# DiffAmp.net
KiCad netlist of a schematic drawn in EAGLE
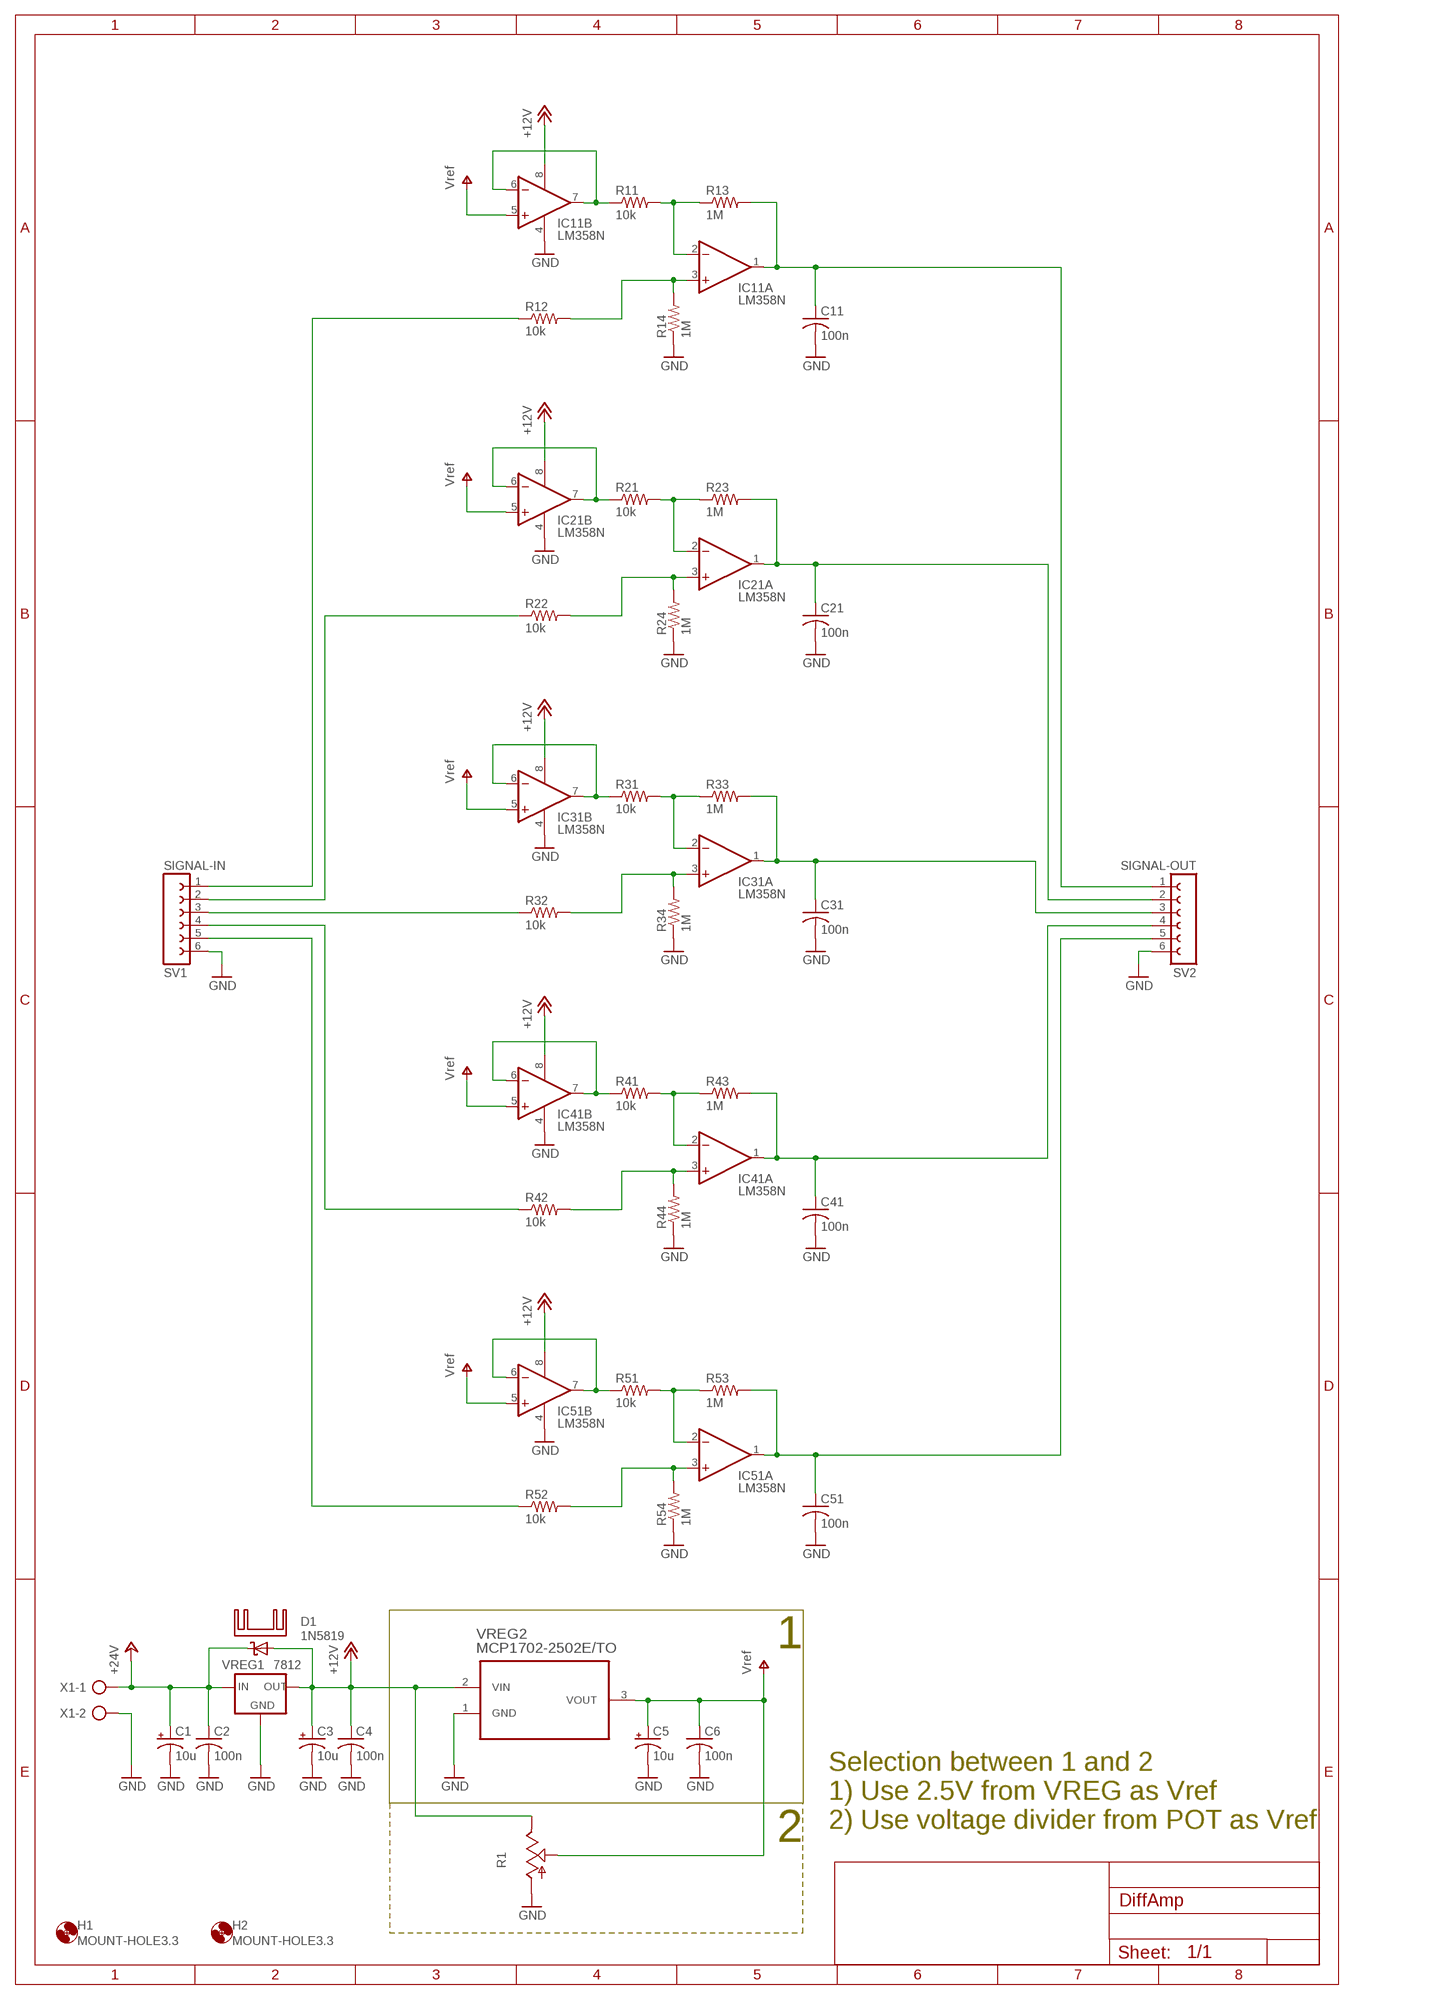
[diagram p0: schematic, sheet 1]

(export (version "E")
  (design (tool "Eeschema 10.0.6"))
  (components
    (comp (ref "C1")
      (value "10u")
      (footprint "eagle-import:E2-5")
      (libsource (lib "eagle-import") (part "CPOL-USE2-5"))
    )
    (comp (ref "C2")
      (value "100n")
      (footprint "eagle-import:C050-025X075")
      (libsource (lib "eagle-import") (part "C-US050-025X075"))
    )
    (comp (ref "C3")
      (value "10u")
      (footprint "eagle-import:E2-5")
      (libsource (lib "eagle-import") (part "CPOL-USE2-5"))
    )
    (comp (ref "C4")
      (value "100n")
      (footprint "eagle-import:C050-025X075")
      (libsource (lib "eagle-import") (part "C-US050-025X075"))
    )
    (comp (ref "C5")
      (value "10u")
      (footprint "eagle-import:E2-5")
      (libsource (lib "eagle-import") (part "CPOL-USE2-5"))
    )
    (comp (ref "C6")
      (value "100n")
      (footprint "eagle-import:C050-025X075")
      (libsource (lib "eagle-import") (part "C-US050-025X075"))
    )
    (comp (ref "C11")
      (value "100n")
      (footprint "eagle-import:C050-025X075")
      (libsource (lib "eagle-import") (part "C-US050-025X075"))
    )
    (comp (ref "C21")
      (value "100n")
      (footprint "eagle-import:C050-025X075")
      (libsource (lib "eagle-import") (part "C-US050-025X075"))
    )
    (comp (ref "C31")
      (value "100n")
      (footprint "eagle-import:C050-025X075")
      (libsource (lib "eagle-import") (part "C-US050-025X075"))
    )
    (comp (ref "C41")
      (value "100n")
      (footprint "eagle-import:C050-025X075")
      (libsource (lib "eagle-import") (part "C-US050-025X075"))
    )
    (comp (ref "C51")
      (value "100n")
      (footprint "eagle-import:C050-025X075")
      (libsource (lib "eagle-import") (part "C-US050-025X075"))
    )
    (comp (ref "D1")
      (value "1N5819")
      (footprint "eagle-import:DO35-7")
      (libsource (lib "eagle-import") (part "SCHOTTKY-DIODEDO35-7"))
    )
    (comp (ref "H1")
      (value "MOUNT-HOLE3.3")
      (footprint "eagle-import:3,3")
      (libsource (lib "eagle-import") (part "MOUNT-HOLE3.3"))
    )
    (comp (ref "H2")
      (value "MOUNT-HOLE3.3")
      (footprint "eagle-import:3,3")
      (libsource (lib "eagle-import") (part "MOUNT-HOLE3.3"))
    )
    (comp (ref "IC11")
      (value "LM358N")
      (footprint "eagle-import:DIL08")
      (libsource (lib "eagle-import") (part "LM358N"))
    )
    (comp (ref "IC21")
      (value "LM358N")
      (footprint "eagle-import:DIL08")
      (libsource (lib "eagle-import") (part "LM358N"))
    )
    (comp (ref "IC31")
      (value "LM358N")
      (footprint "eagle-import:DIL08")
      (libsource (lib "eagle-import") (part "LM358N"))
    )
    (comp (ref "IC41")
      (value "LM358N")
      (footprint "eagle-import:DIL08")
      (libsource (lib "eagle-import") (part "LM358N"))
    )
    (comp (ref "IC51")
      (value "LM358N")
      (footprint "eagle-import:DIL08")
      (libsource (lib "eagle-import") (part "LM358N"))
    )
    (comp (ref "KK1")
      (value "SK95-2M3")
      (footprint "eagle-import:SK95-2M3")
      (libsource (lib "eagle-import") (part "SK95-2M3"))
    )
    (comp (ref "R1")
      (value "TRIM_US-S64W")
      (footprint "eagle-import:S64W")
      (libsource (lib "eagle-import") (part "TRIM_US-S64W"))
    )
    (comp (ref "R11")
      (value "10k")
      (footprint "eagle-import:0207_7")
      (libsource (lib "eagle-import") (part "R-US_0207/7"))
    )
    (comp (ref "R12")
      (value "10k")
      (footprint "eagle-import:0207_7")
      (libsource (lib "eagle-import") (part "R-US_0207/7"))
    )
    (comp (ref "R13")
      (value "1M")
      (footprint "eagle-import:0207_7")
      (libsource (lib "eagle-import") (part "R-US_0207/7"))
    )
    (comp (ref "R14")
      (value "1M")
      (footprint "eagle-import:0207_7")
      (libsource (lib "eagle-import") (part "R-US_0207/7"))
    )
    (comp (ref "R21")
      (value "10k")
      (footprint "eagle-import:0207_7")
      (libsource (lib "eagle-import") (part "R-US_0207/7"))
    )
    (comp (ref "R22")
      (value "10k")
      (footprint "eagle-import:0207_7")
      (libsource (lib "eagle-import") (part "R-US_0207/7"))
    )
    (comp (ref "R23")
      (value "1M")
      (footprint "eagle-import:0207_7")
      (libsource (lib "eagle-import") (part "R-US_0207/7"))
    )
    (comp (ref "R24")
      (value "1M")
      (footprint "eagle-import:0207_7")
      (libsource (lib "eagle-import") (part "R-US_0207/7"))
    )
    (comp (ref "R31")
      (value "10k")
      (footprint "eagle-import:0207_7")
      (libsource (lib "eagle-import") (part "R-US_0207/7"))
    )
    (comp (ref "R32")
      (value "10k")
      (footprint "eagle-import:0207_7")
      (libsource (lib "eagle-import") (part "R-US_0207/7"))
    )
    (comp (ref "R33")
      (value "1M")
      (footprint "eagle-import:0207_7")
      (libsource (lib "eagle-import") (part "R-US_0207/7"))
    )
    (comp (ref "R34")
      (value "1M")
      (footprint "eagle-import:0207_7")
      (libsource (lib "eagle-import") (part "R-US_0207/7"))
    )
    (comp (ref "R41")
      (value "10k")
      (footprint "eagle-import:0207_7")
      (libsource (lib "eagle-import") (part "R-US_0207/7"))
    )
    (comp (ref "R42")
      (value "10k")
      (footprint "eagle-import:0207_7")
      (libsource (lib "eagle-import") (part "R-US_0207/7"))
    )
    (comp (ref "R43")
      (value "1M")
      (footprint "eagle-import:0207_7")
      (libsource (lib "eagle-import") (part "R-US_0207/7"))
    )
    (comp (ref "R44")
      (value "1M")
      (footprint "eagle-import:0207_7")
      (libsource (lib "eagle-import") (part "R-US_0207/7"))
    )
    (comp (ref "R51")
      (value "10k")
      (footprint "eagle-import:0207_7")
      (libsource (lib "eagle-import") (part "R-US_0207/7"))
    )
    (comp (ref "R52")
      (value "10k")
      (footprint "eagle-import:0207_7")
      (libsource (lib "eagle-import") (part "R-US_0207/7"))
    )
    (comp (ref "R53")
      (value "1M")
      (footprint "eagle-import:0207_7")
      (libsource (lib "eagle-import") (part "R-US_0207/7"))
    )
    (comp (ref "R54")
      (value "1M")
      (footprint "eagle-import:0207_7")
      (libsource (lib "eagle-import") (part "R-US_0207/7"))
    )
    (comp (ref "SV1")
      (value "SIGNAL-IN")
      (footprint "eagle-import:FE06")
      (libsource (lib "eagle-import") (part "FE06-1"))
    )
    (comp (ref "SV2")
      (value "SIGNAL-OUT")
      (footprint "eagle-import:FE06")
      (libsource (lib "eagle-import") (part "FE06-1"))
    )
    (comp (ref "VREG1")
      (value "7812")
      (footprint "eagle-import:78XXS")
      (libsource (lib "eagle-import") (part "78XXS"))
    )
    (comp (ref "VREG2")
      (value "MCP1702-2502E/TO")
      (footprint "eagle-import:TO127P254X533-3")
      (fields (field (name "MPN") "MCP1702-3302E/TO"))
      (libsource (lib "eagle-import") (part "MCP1702-3302E/TO"))
    )
    (comp (ref "X1")
      (value "AK500/2")
      (footprint "eagle-import:AK500_2")
      (libsource (lib "eagle-import") (part "AK500/2"))
    )
  )
  (nets
    (net (code "1") (name "+12V") (class "Default")
      (node (ref "C3") (pin "+") (pinfunction "+_+") (pintype "passive"))
      (node (ref "C4") (pin "1") (pinfunction "1_1") (pintype "passive"))
      (node (ref "D1") (pin "A") (pinfunction "A_A") (pintype "passive"))
      (node (ref "IC11") (pin "8") (pinfunction "V+_8") (pintype "power_in"))
      (node (ref "IC21") (pin "8") (pinfunction "V+_8") (pintype "power_in"))
      (node (ref "IC31") (pin "8") (pinfunction "V+_8") (pintype "power_in"))
      (node (ref "IC41") (pin "8") (pinfunction "V+_8") (pintype "power_in"))
      (node (ref "IC51") (pin "8") (pinfunction "V+_8") (pintype "power_in"))
      (node (ref "R1") (pin "E") (pinfunction "E_E") (pintype "passive"))
      (node (ref "VREG1") (pin "OUT") (pinfunction "OUT_OUT") (pintype "passive"))
      (node (ref "VREG2") (pin "2") (pinfunction "VIN_2") (pintype "input"))
    )
    (net (code "2") (name "+24V") (class "Default")
      (node (ref "C1") (pin "+") (pinfunction "+_+") (pintype "passive"))
      (node (ref "C2") (pin "1") (pinfunction "1_1") (pintype "passive"))
      (node (ref "D1") (pin "C") (pinfunction "C_C") (pintype "passive"))
      (node (ref "VREG1") (pin "IN") (pinfunction "IN_IN") (pintype "input"))
      (node (ref "X1") (pin "1") (pinfunction "KL_1") (pintype "passive"))
    )
    (net (code "3") (name "GND") (class "Default")
      (node (ref "C1") (pin "-") (pinfunction "-_-") (pintype "passive"))
      (node (ref "C11") (pin "2") (pinfunction "2_2") (pintype "passive"))
      (node (ref "C2") (pin "2") (pinfunction "2_2") (pintype "passive"))
      (node (ref "C21") (pin "2") (pinfunction "2_2") (pintype "passive"))
      (node (ref "C3") (pin "-") (pinfunction "-_-") (pintype "passive"))
      (node (ref "C31") (pin "2") (pinfunction "2_2") (pintype "passive"))
      (node (ref "C4") (pin "2") (pinfunction "2_2") (pintype "passive"))
      (node (ref "C41") (pin "2") (pinfunction "2_2") (pintype "passive"))
      (node (ref "C5") (pin "-") (pinfunction "-_-") (pintype "passive"))
      (node (ref "C51") (pin "2") (pinfunction "2_2") (pintype "passive"))
      (node (ref "C6") (pin "2") (pinfunction "2_2") (pintype "passive"))
      (node (ref "IC11") (pin "4") (pinfunction "V-_4") (pintype "power_in"))
      (node (ref "IC21") (pin "4") (pinfunction "V-_4") (pintype "power_in"))
      (node (ref "IC31") (pin "4") (pinfunction "V-_4") (pintype "power_in"))
      (node (ref "IC41") (pin "4") (pinfunction "V-_4") (pintype "power_in"))
      (node (ref "IC51") (pin "4") (pinfunction "V-_4") (pintype "power_in"))
      (node (ref "R1") (pin "A") (pinfunction "A_A") (pintype "passive"))
      (node (ref "R14") (pin "1") (pinfunction "1_1") (pintype "passive"))
      (node (ref "R24") (pin "1") (pinfunction "1_1") (pintype "passive"))
      (node (ref "R34") (pin "1") (pinfunction "1_1") (pintype "passive"))
      (node (ref "R44") (pin "1") (pinfunction "1_1") (pintype "passive"))
      (node (ref "R54") (pin "1") (pinfunction "1_1") (pintype "passive"))
      (node (ref "SV1") (pin "6") (pinfunction "6_6") (pintype "passive"))
      (node (ref "SV2") (pin "6") (pinfunction "6_6") (pintype "passive"))
      (node (ref "VREG1") (pin "GND") (pinfunction "GND_GND") (pintype "input"))
      (node (ref "VREG2") (pin "1") (pinfunction "GND_1") (pintype "passive"))
      (node (ref "X1") (pin "2") (pinfunction "KL_2") (pintype "passive"))
    )
    (net (code "4") (name "Net-(IC11A-+IN)") (class "Default")
      (node (ref "IC11") (pin "3") (pinfunction "+IN_3") (pintype "input"))
      (node (ref "R12") (pin "2") (pinfunction "2_2") (pintype "passive"))
      (node (ref "R14") (pin "2") (pinfunction "2_2") (pintype "passive"))
    )
    (net (code "5") (name "Net-(IC11A--IN)") (class "Default")
      (node (ref "IC11") (pin "2") (pinfunction "-IN_2") (pintype "input"))
      (node (ref "R11") (pin "2") (pinfunction "2_2") (pintype "passive"))
      (node (ref "R13") (pin "1") (pinfunction "1_1") (pintype "passive"))
    )
    (net (code "6") (name "Net-(IC11A-OUT)") (class "Default")
      (node (ref "C11") (pin "1") (pinfunction "1_1") (pintype "passive"))
      (node (ref "IC11") (pin "1") (pinfunction "OUT_1") (pintype "output"))
      (node (ref "R13") (pin "2") (pinfunction "2_2") (pintype "passive"))
      (node (ref "SV2") (pin "1") (pinfunction "1_1") (pintype "passive"))
    )
    (net (code "7") (name "Net-(IC11B--IN)") (class "Default")
      (node (ref "IC11") (pin "6") (pinfunction "-IN_6") (pintype "input"))
      (node (ref "IC11") (pin "7") (pinfunction "OUT_7") (pintype "output"))
      (node (ref "R11") (pin "1") (pinfunction "1_1") (pintype "passive"))
    )
    (net (code "8") (name "Net-(IC21A-+IN)") (class "Default")
      (node (ref "IC21") (pin "3") (pinfunction "+IN_3") (pintype "input"))
      (node (ref "R22") (pin "2") (pinfunction "2_2") (pintype "passive"))
      (node (ref "R24") (pin "2") (pinfunction "2_2") (pintype "passive"))
    )
    (net (code "9") (name "Net-(IC21A--IN)") (class "Default")
      (node (ref "IC21") (pin "2") (pinfunction "-IN_2") (pintype "input"))
      (node (ref "R21") (pin "2") (pinfunction "2_2") (pintype "passive"))
      (node (ref "R23") (pin "1") (pinfunction "1_1") (pintype "passive"))
    )
    (net (code "10") (name "Net-(IC21A-OUT)") (class "Default")
      (node (ref "C21") (pin "1") (pinfunction "1_1") (pintype "passive"))
      (node (ref "IC21") (pin "1") (pinfunction "OUT_1") (pintype "output"))
      (node (ref "R23") (pin "2") (pinfunction "2_2") (pintype "passive"))
      (node (ref "SV2") (pin "2") (pinfunction "2_2") (pintype "passive"))
    )
    (net (code "11") (name "Net-(IC21B--IN)") (class "Default")
      (node (ref "IC21") (pin "6") (pinfunction "-IN_6") (pintype "input"))
      (node (ref "IC21") (pin "7") (pinfunction "OUT_7") (pintype "output"))
      (node (ref "R21") (pin "1") (pinfunction "1_1") (pintype "passive"))
    )
    (net (code "12") (name "Net-(IC31A-+IN)") (class "Default")
      (node (ref "IC31") (pin "3") (pinfunction "+IN_3") (pintype "input"))
      (node (ref "R32") (pin "2") (pinfunction "2_2") (pintype "passive"))
      (node (ref "R34") (pin "2") (pinfunction "2_2") (pintype "passive"))
    )
    (net (code "13") (name "Net-(IC31A--IN)") (class "Default")
      (node (ref "IC31") (pin "2") (pinfunction "-IN_2") (pintype "input"))
      (node (ref "R31") (pin "2") (pinfunction "2_2") (pintype "passive"))
      (node (ref "R33") (pin "1") (pinfunction "1_1") (pintype "passive"))
    )
    (net (code "14") (name "Net-(IC31A-OUT)") (class "Default")
      (node (ref "C31") (pin "1") (pinfunction "1_1") (pintype "passive"))
      (node (ref "IC31") (pin "1") (pinfunction "OUT_1") (pintype "output"))
      (node (ref "R33") (pin "2") (pinfunction "2_2") (pintype "passive"))
      (node (ref "SV2") (pin "3") (pinfunction "3_3") (pintype "passive"))
    )
    (net (code "15") (name "Net-(IC31B--IN)") (class "Default")
      (node (ref "IC31") (pin "6") (pinfunction "-IN_6") (pintype "input"))
      (node (ref "IC31") (pin "7") (pinfunction "OUT_7") (pintype "output"))
      (node (ref "R31") (pin "1") (pinfunction "1_1") (pintype "passive"))
    )
    (net (code "16") (name "Net-(IC41A-+IN)") (class "Default")
      (node (ref "IC41") (pin "3") (pinfunction "+IN_3") (pintype "input"))
      (node (ref "R42") (pin "2") (pinfunction "2_2") (pintype "passive"))
      (node (ref "R44") (pin "2") (pinfunction "2_2") (pintype "passive"))
    )
    (net (code "17") (name "Net-(IC41A--IN)") (class "Default")
      (node (ref "IC41") (pin "2") (pinfunction "-IN_2") (pintype "input"))
      (node (ref "R41") (pin "2") (pinfunction "2_2") (pintype "passive"))
      (node (ref "R43") (pin "1") (pinfunction "1_1") (pintype "passive"))
    )
    (net (code "18") (name "Net-(IC41A-OUT)") (class "Default")
      (node (ref "C41") (pin "1") (pinfunction "1_1") (pintype "passive"))
      (node (ref "IC41") (pin "1") (pinfunction "OUT_1") (pintype "output"))
      (node (ref "R43") (pin "2") (pinfunction "2_2") (pintype "passive"))
      (node (ref "SV2") (pin "4") (pinfunction "4_4") (pintype "passive"))
    )
    (net (code "19") (name "Net-(IC41B--IN)") (class "Default")
      (node (ref "IC41") (pin "6") (pinfunction "-IN_6") (pintype "input"))
      (node (ref "IC41") (pin "7") (pinfunction "OUT_7") (pintype "output"))
      (node (ref "R41") (pin "1") (pinfunction "1_1") (pintype "passive"))
    )
    (net (code "20") (name "Net-(IC51A-+IN)") (class "Default")
      (node (ref "IC51") (pin "3") (pinfunction "+IN_3") (pintype "input"))
      (node (ref "R52") (pin "2") (pinfunction "2_2") (pintype "passive"))
      (node (ref "R54") (pin "2") (pinfunction "2_2") (pintype "passive"))
    )
    (net (code "21") (name "Net-(IC51A--IN)") (class "Default")
      (node (ref "IC51") (pin "2") (pinfunction "-IN_2") (pintype "input"))
      (node (ref "R51") (pin "2") (pinfunction "2_2") (pintype "passive"))
      (node (ref "R53") (pin "1") (pinfunction "1_1") (pintype "passive"))
    )
    (net (code "22") (name "Net-(IC51A-OUT)") (class "Default")
      (node (ref "C51") (pin "1") (pinfunction "1_1") (pintype "passive"))
      (node (ref "IC51") (pin "1") (pinfunction "OUT_1") (pintype "output"))
      (node (ref "R53") (pin "2") (pinfunction "2_2") (pintype "passive"))
      (node (ref "SV2") (pin "5") (pinfunction "5_5") (pintype "passive"))
    )
    (net (code "23") (name "Net-(IC51B--IN)") (class "Default")
      (node (ref "IC51") (pin "6") (pinfunction "-IN_6") (pintype "input"))
      (node (ref "IC51") (pin "7") (pinfunction "OUT_7") (pintype "output"))
      (node (ref "R51") (pin "1") (pinfunction "1_1") (pintype "passive"))
    )
    (net (code "24") (name "Net-(R12-Pad1)") (class "Default")
      (node (ref "R12") (pin "1") (pinfunction "1_1") (pintype "passive"))
      (node (ref "SV1") (pin "1") (pinfunction "1_1") (pintype "passive"))
    )
    (net (code "25") (name "Net-(R22-Pad1)") (class "Default")
      (node (ref "R22") (pin "1") (pinfunction "1_1") (pintype "passive"))
      (node (ref "SV1") (pin "2") (pinfunction "2_2") (pintype "passive"))
    )
    (net (code "26") (name "Net-(R32-Pad1)") (class "Default")
      (node (ref "R32") (pin "1") (pinfunction "1_1") (pintype "passive"))
      (node (ref "SV1") (pin "3") (pinfunction "3_3") (pintype "passive"))
    )
    (net (code "27") (name "Net-(R42-Pad1)") (class "Default")
      (node (ref "R42") (pin "1") (pinfunction "1_1") (pintype "passive"))
      (node (ref "SV1") (pin "4") (pinfunction "4_4") (pintype "passive"))
    )
    (net (code "28") (name "Net-(R52-Pad1)") (class "Default")
      (node (ref "R52") (pin "1") (pinfunction "1_1") (pintype "passive"))
      (node (ref "SV1") (pin "5") (pinfunction "5_5") (pintype "passive"))
    )
    (net (code "29") (name "Vref") (class "Default")
      (node (ref "C5") (pin "+") (pinfunction "+_+") (pintype "passive"))
      (node (ref "C6") (pin "1") (pinfunction "1_1") (pintype "passive"))
      (node (ref "IC11") (pin "5") (pinfunction "+IN_5") (pintype "input"))
      (node (ref "IC21") (pin "5") (pinfunction "+IN_5") (pintype "input"))
      (node (ref "IC31") (pin "5") (pinfunction "+IN_5") (pintype "input"))
      (node (ref "IC41") (pin "5") (pinfunction "+IN_5") (pintype "input"))
      (node (ref "IC51") (pin "5") (pinfunction "+IN_5") (pintype "input"))
      (node (ref "R1") (pin "S") (pinfunction "S_S") (pintype "passive"))
      (node (ref "VREG2") (pin "3") (pinfunction "VOUT_3") (pintype "output"))
    )
  )
)
